# untitled.net
KiCad netlist of a schematic drawn in EAGLE
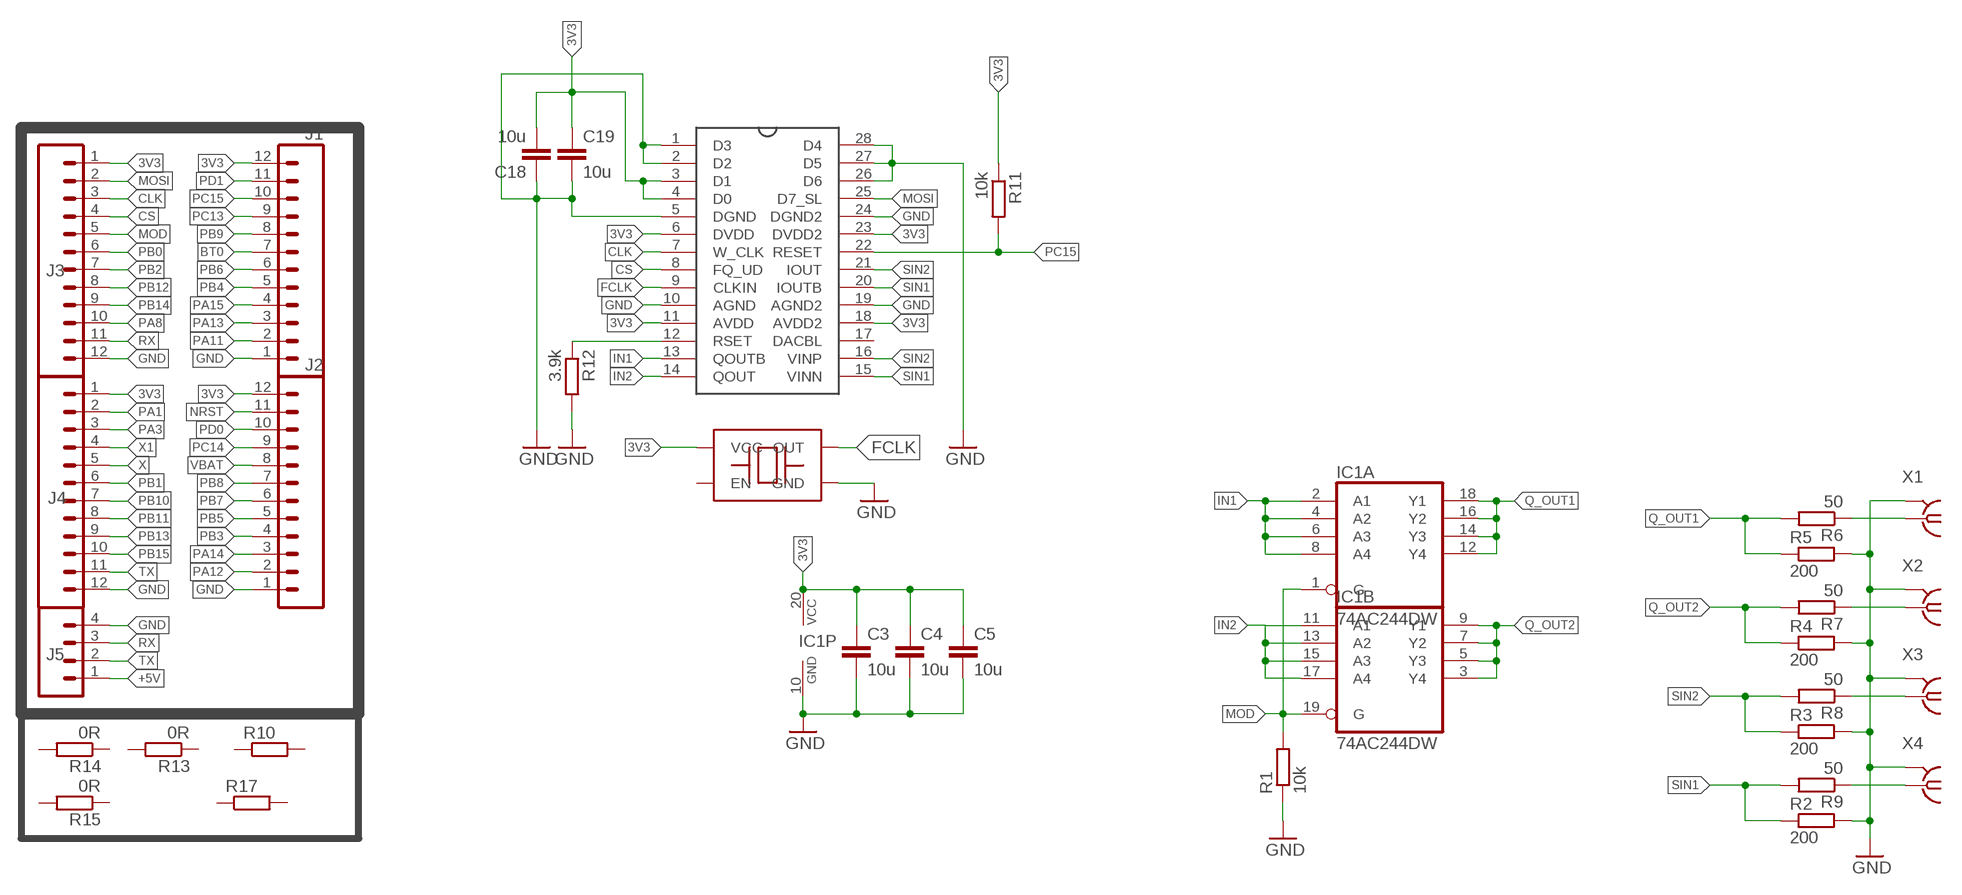
[diagram p0: schematic, sheet 1]

(export (version "E")
  (design (tool "Eeschema 10.0.6"))
  (components
    (comp (ref "C3")
      (value "10u")
      (footprint "eagle-import:0805")
      (libsource (lib "eagle-import") (part "C0805"))
    )
    (comp (ref "C4")
      (value "10u")
      (footprint "eagle-import:0805")
      (libsource (lib "eagle-import") (part "C0805"))
    )
    (comp (ref "C5")
      (value "10u")
      (footprint "eagle-import:0805")
      (libsource (lib "eagle-import") (part "C0805"))
    )
    (comp (ref "C18")
      (value "10u")
      (footprint "eagle-import:0805")
      (libsource (lib "eagle-import") (part "C0805"))
    )
    (comp (ref "C19")
      (value "10u")
      (footprint "eagle-import:0805")
      (libsource (lib "eagle-import") (part "C0805"))
    )
    (comp (ref "IC1")
      (value "74AC244DW")
      (footprint "eagle-import:SO20W")
      (libsource (lib "eagle-import") (part "74244DWAC"))
    )
    (comp (ref "J1")
      (value "M12PTH")
      (footprint "eagle-import:1X12")
      (libsource (lib "eagle-import") (part "M12PTH"))
    )
    (comp (ref "J2")
      (value "M12PTH")
      (footprint "eagle-import:1X12")
      (libsource (lib "eagle-import") (part "M12PTH"))
    )
    (comp (ref "J3")
      (value "M12PTH")
      (footprint "eagle-import:1X12")
      (libsource (lib "eagle-import") (part "M12PTH"))
    )
    (comp (ref "J4")
      (value "M12PTH")
      (footprint "eagle-import:1X12")
      (libsource (lib "eagle-import") (part "M12PTH"))
    )
    (comp (ref "J5")
      (value "M04PTH")
      (footprint "eagle-import:1X04")
      (libsource (lib "eagle-import") (part "M04PTH"))
    )
    (comp (ref "R1")
      (value "10k")
      (footprint "eagle-import:0805")
      (libsource (lib "eagle-import") (part "R0805"))
    )
    (comp (ref "R2")
      (value "200")
      (footprint "eagle-import:0805")
      (libsource (lib "eagle-import") (part "R0805"))
    )
    (comp (ref "R3")
      (value "200")
      (footprint "eagle-import:0805")
      (libsource (lib "eagle-import") (part "R0805"))
    )
    (comp (ref "R4")
      (value "200")
      (footprint "eagle-import:0805")
      (libsource (lib "eagle-import") (part "R0805"))
    )
    (comp (ref "R5")
      (value "200")
      (footprint "eagle-import:0805")
      (libsource (lib "eagle-import") (part "R0805"))
    )
    (comp (ref "R6")
      (value "50")
      (footprint "eagle-import:0805")
      (libsource (lib "eagle-import") (part "R0805"))
    )
    (comp (ref "R7")
      (value "50")
      (footprint "eagle-import:0805")
      (libsource (lib "eagle-import") (part "R0805"))
    )
    (comp (ref "R8")
      (value "50")
      (footprint "eagle-import:0805")
      (libsource (lib "eagle-import") (part "R0805"))
    )
    (comp (ref "R9")
      (value "50")
      (footprint "eagle-import:0805")
      (libsource (lib "eagle-import") (part "R0805"))
    )
    (comp (ref "R10")
      (value "R0805")
      (footprint "eagle-import:0805")
      (libsource (lib "eagle-import") (part "R0805"))
    )
    (comp (ref "R11")
      (value "10k")
      (footprint "eagle-import:0805")
      (libsource (lib "eagle-import") (part "R0805"))
    )
    (comp (ref "R12")
      (value "3.9k")
      (footprint "eagle-import:0805")
      (libsource (lib "eagle-import") (part "R0805"))
    )
    (comp (ref "R13")
      (value "0R")
      (footprint "eagle-import:0805")
      (libsource (lib "eagle-import") (part "R0805"))
    )
    (comp (ref "R14")
      (value "0R")
      (footprint "eagle-import:1206")
      (libsource (lib "eagle-import") (part "R1206"))
    )
    (comp (ref "R15")
      (value "0R")
      (footprint "eagle-import:0805")
      (libsource (lib "eagle-import") (part "R0805"))
    )
    (comp (ref "R17")
      (value "R1206")
      (footprint "eagle-import:1206")
      (libsource (lib "eagle-import") (part "R1206"))
    )
    (comp (ref "U$1")
      (value "AD9850")
      (footprint "eagle-import:SSOP28")
      (libsource (lib "eagle-import") (part "AD9850"))
    )
    (comp (ref "U$3")
      (value "TXC-BA")
      (footprint "eagle-import:7X5")
      (libsource (lib "eagle-import") (part "TXC-BA"))
    )
    (comp (ref "X1")
      (value "BU-SMA-H")
      (footprint "eagle-import:BU-SMA-H")
      (libsource (lib "eagle-import") (part "BU-SMA-H"))
    )
    (comp (ref "X2")
      (value "BU-SMA-H")
      (footprint "eagle-import:BU-SMA-H")
      (libsource (lib "eagle-import") (part "BU-SMA-H"))
    )
    (comp (ref "X3")
      (value "BU-SMA-H")
      (footprint "eagle-import:BU-SMA-H")
      (libsource (lib "eagle-import") (part "BU-SMA-H"))
    )
    (comp (ref "X4")
      (value "BU-SMA-H")
      (footprint "eagle-import:BU-SMA-H")
      (libsource (lib "eagle-import") (part "BU-SMA-H"))
    )
  )
  (nets
    (net (code "1") (name "+5V") (class "Default")
      (node (ref "J5") (pin "1") (pinfunction "1_1") (pintype "passive"))
    )
    (net (code "2") (name "3V3") (class "Default")
      (node (ref "C18") (pin "2") (pinfunction "2_2") (pintype "passive"))
      (node (ref "C19") (pin "1") (pinfunction "1_1") (pintype "passive"))
      (node (ref "C3") (pin "1") (pinfunction "1_1") (pintype "passive"))
      (node (ref "C4") (pin "1") (pinfunction "1_1") (pintype "passive"))
      (node (ref "C5") (pin "1") (pinfunction "1_1") (pintype "passive"))
      (node (ref "IC1") (pin "20") (pinfunction "VCC_20") (pintype "power_in"))
      (node (ref "J1") (pin "12") (pinfunction "12_12") (pintype "passive"))
      (node (ref "J2") (pin "12") (pinfunction "12_12") (pintype "passive"))
      (node (ref "J3") (pin "1") (pinfunction "1_1") (pintype "passive"))
      (node (ref "J4") (pin "1") (pinfunction "1_1") (pintype "passive"))
      (node (ref "R11") (pin "1") (pinfunction "1_1") (pintype "passive"))
      (node (ref "U$1") (pin "11") (pinfunction "AVDD_11") (pintype "power_in"))
      (node (ref "U$1") (pin "18") (pinfunction "AVDD2_18") (pintype "power_in"))
      (node (ref "U$1") (pin "23") (pinfunction "DVDD2_23") (pintype "power_in"))
      (node (ref "U$1") (pin "3") (pinfunction "D1_3") (pintype "input"))
      (node (ref "U$1") (pin "4") (pinfunction "D0_4") (pintype "bidirectional"))
      (node (ref "U$1") (pin "6") (pinfunction "DVDD_6") (pintype "power_in"))
      (node (ref "U$3") (pin "VCC") (pinfunction "VCC_VCC") (pintype "bidirectional"))
    )
    (net (code "3") (name "BT0") (class "Default")
      (node (ref "J1") (pin "7") (pinfunction "7_7") (pintype "passive"))
    )
    (net (code "4") (name "CLK") (class "Default")
      (node (ref "J3") (pin "3") (pinfunction "3_3") (pintype "passive"))
      (node (ref "U$1") (pin "7") (pinfunction "W_CLK_7") (pintype "bidirectional"))
    )
    (net (code "5") (name "CS") (class "Default")
      (node (ref "J3") (pin "4") (pinfunction "4_4") (pintype "passive"))
      (node (ref "U$1") (pin "8") (pinfunction "FQ_UD_8") (pintype "bidirectional"))
    )
    (net (code "6") (name "FCLK") (class "Default")
      (node (ref "U$1") (pin "9") (pinfunction "CLKIN_9") (pintype "input"))
      (node (ref "U$3") (pin "OUT") (pinfunction "OUT_OUT") (pintype "bidirectional"))
    )
    (net (code "7") (name "GND") (class "Default")
      (node (ref "C18") (pin "1") (pinfunction "1_1") (pintype "passive"))
      (node (ref "C19") (pin "2") (pinfunction "2_2") (pintype "passive"))
      (node (ref "C3") (pin "2") (pinfunction "2_2") (pintype "passive"))
      (node (ref "C4") (pin "2") (pinfunction "2_2") (pintype "passive"))
      (node (ref "C5") (pin "2") (pinfunction "2_2") (pintype "passive"))
      (node (ref "IC1") (pin "10") (pinfunction "GND_10") (pintype "power_in"))
      (node (ref "J1") (pin "1") (pinfunction "1_1") (pintype "passive"))
      (node (ref "J2") (pin "1") (pinfunction "1_1") (pintype "passive"))
      (node (ref "J3") (pin "12") (pinfunction "12_12") (pintype "passive"))
      (node (ref "J4") (pin "12") (pinfunction "12_12") (pintype "passive"))
      (node (ref "J5") (pin "4") (pinfunction "4_4") (pintype "passive"))
      (node (ref "R1") (pin "1") (pinfunction "1_1") (pintype "passive"))
      (node (ref "R12") (pin "2") (pinfunction "2_2") (pintype "passive"))
      (node (ref "R2") (pin "2") (pinfunction "2_2") (pintype "passive"))
      (node (ref "R3") (pin "2") (pinfunction "2_2") (pintype "passive"))
      (node (ref "R4") (pin "2") (pinfunction "2_2") (pintype "passive"))
      (node (ref "R5") (pin "2") (pinfunction "2_2") (pintype "passive"))
      (node (ref "U$1") (pin "1") (pinfunction "D3_1") (pintype "input"))
      (node (ref "U$1") (pin "10") (pinfunction "AGND_10") (pintype "power_in"))
      (node (ref "U$1") (pin "19") (pinfunction "AGND2_19") (pintype "power_in"))
      (node (ref "U$1") (pin "2") (pinfunction "D2_2") (pintype "input"))
      (node (ref "U$1") (pin "24") (pinfunction "DGND2_24") (pintype "power_in"))
      (node (ref "U$1") (pin "26") (pinfunction "D6_26") (pintype "input"))
      (node (ref "U$1") (pin "27") (pinfunction "D5_27") (pintype "input"))
      (node (ref "U$1") (pin "28") (pinfunction "D4_28") (pintype "input"))
      (node (ref "U$1") (pin "5") (pinfunction "DGND_5") (pintype "power_in"))
      (node (ref "U$3") (pin "GND") (pinfunction "GND_GND") (pintype "bidirectional"))
      (node (ref "X1") (pin "2") (pinfunction "2_2") (pintype "passive"))
      (node (ref "X1") (pin "3") (pinfunction "2_3") (pintype "passive"))
      (node (ref "X1") (pin "4") (pinfunction "2_4") (pintype "passive"))
      (node (ref "X1") (pin "5") (pinfunction "2_5") (pintype "passive"))
      (node (ref "X2") (pin "2") (pinfunction "2_2") (pintype "passive"))
      (node (ref "X2") (pin "3") (pinfunction "2_3") (pintype "passive"))
      (node (ref "X2") (pin "4") (pinfunction "2_4") (pintype "passive"))
      (node (ref "X2") (pin "5") (pinfunction "2_5") (pintype "passive"))
      (node (ref "X3") (pin "2") (pinfunction "2_2") (pintype "passive"))
      (node (ref "X3") (pin "3") (pinfunction "2_3") (pintype "passive"))
      (node (ref "X3") (pin "4") (pinfunction "2_4") (pintype "passive"))
      (node (ref "X3") (pin "5") (pinfunction "2_5") (pintype "passive"))
      (node (ref "X4") (pin "2") (pinfunction "2_2") (pintype "passive"))
      (node (ref "X4") (pin "3") (pinfunction "2_3") (pintype "passive"))
      (node (ref "X4") (pin "4") (pinfunction "2_4") (pintype "passive"))
      (node (ref "X4") (pin "5") (pinfunction "2_5") (pintype "passive"))
    )
    (net (code "8") (name "IN1") (class "Default")
      (node (ref "IC1") (pin "2") (pinfunction "A1_2") (pintype "input"))
      (node (ref "IC1") (pin "4") (pinfunction "A2_4") (pintype "input"))
      (node (ref "IC1") (pin "6") (pinfunction "A3_6") (pintype "input"))
      (node (ref "IC1") (pin "8") (pinfunction "A4_8") (pintype "input"))
      (node (ref "U$1") (pin "13") (pinfunction "QOUTB_13") (pintype "output"))
    )
    (net (code "9") (name "IN2") (class "Default")
      (node (ref "IC1") (pin "11") (pinfunction "A1_11") (pintype "input"))
      (node (ref "IC1") (pin "13") (pinfunction "A2_13") (pintype "input"))
      (node (ref "IC1") (pin "15") (pinfunction "A3_15") (pintype "input"))
      (node (ref "IC1") (pin "17") (pinfunction "A4_17") (pintype "input"))
      (node (ref "U$1") (pin "14") (pinfunction "QOUT_14") (pintype "output"))
    )
    (net (code "10") (name "MOD") (class "Default")
      (node (ref "IC1") (pin "1") (pinfunction "G_1") (pintype "input"))
      (node (ref "IC1") (pin "19") (pinfunction "G_19") (pintype "input"))
      (node (ref "J3") (pin "5") (pinfunction "5_5") (pintype "passive"))
      (node (ref "R1") (pin "2") (pinfunction "2_2") (pintype "passive"))
    )
    (net (code "11") (name "MOSI") (class "Default")
      (node (ref "J3") (pin "2") (pinfunction "2_2") (pintype "passive"))
      (node (ref "U$1") (pin "25") (pinfunction "D7_SL_25") (pintype "input"))
    )
    (net (code "12") (name "NRST") (class "Default")
      (node (ref "J2") (pin "11") (pinfunction "11_11") (pintype "passive"))
    )
    (net (code "13") (name "Net-(R6-Pad1)") (class "Default")
      (node (ref "R6") (pin "1") (pinfunction "1_1") (pintype "passive"))
      (node (ref "X1") (pin "1") (pinfunction "1_1") (pintype "passive"))
    )
    (net (code "14") (name "Net-(R7-Pad1)") (class "Default")
      (node (ref "R7") (pin "1") (pinfunction "1_1") (pintype "passive"))
      (node (ref "X2") (pin "1") (pinfunction "1_1") (pintype "passive"))
    )
    (net (code "15") (name "Net-(R8-Pad1)") (class "Default")
      (node (ref "R8") (pin "1") (pinfunction "1_1") (pintype "passive"))
      (node (ref "X3") (pin "1") (pinfunction "1_1") (pintype "passive"))
    )
    (net (code "16") (name "Net-(R9-Pad1)") (class "Default")
      (node (ref "R9") (pin "1") (pinfunction "1_1") (pintype "passive"))
      (node (ref "X4") (pin "1") (pinfunction "1_1") (pintype "passive"))
    )
    (net (code "17") (name "Net-(U$1-RSET)") (class "Default")
      (node (ref "R12") (pin "1") (pinfunction "1_1") (pintype "passive"))
      (node (ref "U$1") (pin "12") (pinfunction "RSET_12") (pintype "input"))
    )
    (net (code "18") (name "PA1") (class "Default")
      (node (ref "J4") (pin "2") (pinfunction "2_2") (pintype "passive"))
    )
    (net (code "19") (name "PA3") (class "Default")
      (node (ref "J4") (pin "3") (pinfunction "3_3") (pintype "passive"))
    )
    (net (code "20") (name "PA8") (class "Default")
      (node (ref "J3") (pin "10") (pinfunction "10_10") (pintype "passive"))
    )
    (net (code "21") (name "PA11") (class "Default")
      (node (ref "J1") (pin "2") (pinfunction "2_2") (pintype "passive"))
    )
    (net (code "22") (name "PA12") (class "Default")
      (node (ref "J2") (pin "2") (pinfunction "2_2") (pintype "passive"))
    )
    (net (code "23") (name "PA13") (class "Default")
      (node (ref "J1") (pin "3") (pinfunction "3_3") (pintype "passive"))
    )
    (net (code "24") (name "PA14") (class "Default")
      (node (ref "J2") (pin "3") (pinfunction "3_3") (pintype "passive"))
    )
    (net (code "25") (name "PA15") (class "Default")
      (node (ref "J1") (pin "4") (pinfunction "4_4") (pintype "passive"))
    )
    (net (code "26") (name "PB0") (class "Default")
      (node (ref "J3") (pin "6") (pinfunction "6_6") (pintype "passive"))
    )
    (net (code "27") (name "PB1") (class "Default")
      (node (ref "J4") (pin "6") (pinfunction "6_6") (pintype "passive"))
    )
    (net (code "28") (name "PB2") (class "Default")
      (node (ref "J3") (pin "7") (pinfunction "7_7") (pintype "passive"))
    )
    (net (code "29") (name "PB3") (class "Default")
      (node (ref "J2") (pin "4") (pinfunction "4_4") (pintype "passive"))
    )
    (net (code "30") (name "PB4") (class "Default")
      (node (ref "J1") (pin "5") (pinfunction "5_5") (pintype "passive"))
    )
    (net (code "31") (name "PB5") (class "Default")
      (node (ref "J2") (pin "5") (pinfunction "5_5") (pintype "passive"))
    )
    (net (code "32") (name "PB6") (class "Default")
      (node (ref "J1") (pin "6") (pinfunction "6_6") (pintype "passive"))
    )
    (net (code "33") (name "PB7") (class "Default")
      (node (ref "J2") (pin "6") (pinfunction "6_6") (pintype "passive"))
    )
    (net (code "34") (name "PB8") (class "Default")
      (node (ref "J2") (pin "7") (pinfunction "7_7") (pintype "passive"))
    )
    (net (code "35") (name "PB9") (class "Default")
      (node (ref "J1") (pin "8") (pinfunction "8_8") (pintype "passive"))
    )
    (net (code "36") (name "PB10") (class "Default")
      (node (ref "J4") (pin "7") (pinfunction "7_7") (pintype "passive"))
    )
    (net (code "37") (name "PB11") (class "Default")
      (node (ref "J4") (pin "8") (pinfunction "8_8") (pintype "passive"))
    )
    (net (code "38") (name "PB12") (class "Default")
      (node (ref "J3") (pin "8") (pinfunction "8_8") (pintype "passive"))
    )
    (net (code "39") (name "PB13") (class "Default")
      (node (ref "J4") (pin "9") (pinfunction "9_9") (pintype "passive"))
    )
    (net (code "40") (name "PB14") (class "Default")
      (node (ref "J3") (pin "9") (pinfunction "9_9") (pintype "passive"))
    )
    (net (code "41") (name "PB15") (class "Default")
      (node (ref "J4") (pin "10") (pinfunction "10_10") (pintype "passive"))
    )
    (net (code "42") (name "PC13") (class "Default")
      (node (ref "J1") (pin "9") (pinfunction "9_9") (pintype "passive"))
    )
    (net (code "43") (name "PC14") (class "Default")
      (node (ref "J2") (pin "9") (pinfunction "9_9") (pintype "passive"))
    )
    (net (code "44") (name "PC15") (class "Default")
      (node (ref "J1") (pin "10") (pinfunction "10_10") (pintype "passive"))
      (node (ref "R11") (pin "2") (pinfunction "2_2") (pintype "passive"))
      (node (ref "U$1") (pin "22") (pinfunction "RESET_22") (pintype "input"))
    )
    (net (code "45") (name "PD0") (class "Default")
      (node (ref "J2") (pin "10") (pinfunction "10_10") (pintype "passive"))
    )
    (net (code "46") (name "PD1") (class "Default")
      (node (ref "J1") (pin "11") (pinfunction "11_11") (pintype "passive"))
    )
    (net (code "47") (name "Q_OUT1") (class "Default")
      (node (ref "IC1") (pin "12") (pinfunction "Y4_12") (pintype "tri_state"))
      (node (ref "IC1") (pin "14") (pinfunction "Y3_14") (pintype "tri_state"))
      (node (ref "IC1") (pin "16") (pinfunction "Y2_16") (pintype "tri_state"))
      (node (ref "IC1") (pin "18") (pinfunction "Y1_18") (pintype "tri_state"))
      (node (ref "R5") (pin "1") (pinfunction "1_1") (pintype "passive"))
      (node (ref "R6") (pin "2") (pinfunction "2_2") (pintype "passive"))
    )
    (net (code "48") (name "Q_OUT2") (class "Default")
      (node (ref "IC1") (pin "3") (pinfunction "Y4_3") (pintype "tri_state"))
      (node (ref "IC1") (pin "5") (pinfunction "Y3_5") (pintype "tri_state"))
      (node (ref "IC1") (pin "7") (pinfunction "Y2_7") (pintype "tri_state"))
      (node (ref "IC1") (pin "9") (pinfunction "Y1_9") (pintype "tri_state"))
      (node (ref "R4") (pin "1") (pinfunction "1_1") (pintype "passive"))
      (node (ref "R7") (pin "2") (pinfunction "2_2") (pintype "passive"))
    )
    (net (code "49") (name "RX") (class "Default")
      (node (ref "J3") (pin "11") (pinfunction "11_11") (pintype "passive"))
      (node (ref "J5") (pin "3") (pinfunction "3_3") (pintype "passive"))
    )
    (net (code "50") (name "SIN1") (class "Default")
      (node (ref "R2") (pin "1") (pinfunction "1_1") (pintype "passive"))
      (node (ref "R9") (pin "2") (pinfunction "2_2") (pintype "passive"))
      (node (ref "U$1") (pin "15") (pinfunction "VINN_15") (pintype "input"))
      (node (ref "U$1") (pin "20") (pinfunction "IOUTB_20") (pintype "output"))
    )
    (net (code "51") (name "SIN2") (class "Default")
      (node (ref "R3") (pin "1") (pinfunction "1_1") (pintype "passive"))
      (node (ref "R8") (pin "2") (pinfunction "2_2") (pintype "passive"))
      (node (ref "U$1") (pin "16") (pinfunction "VINP_16") (pintype "input"))
      (node (ref "U$1") (pin "21") (pinfunction "IOUT_21") (pintype "output"))
    )
    (net (code "52") (name "TX") (class "Default")
      (node (ref "J4") (pin "11") (pinfunction "11_11") (pintype "passive"))
      (node (ref "J5") (pin "2") (pinfunction "2_2") (pintype "passive"))
    )
    (net (code "53") (name "VBAT") (class "Default")
      (node (ref "J2") (pin "8") (pinfunction "8_8") (pintype "passive"))
    )
    (net (code "54") (name "X") (class "Default")
      (node (ref "J4") (pin "5") (pinfunction "5_5") (pintype "passive"))
    )
    (net (code "55") (name "X1") (class "Default")
      (node (ref "J4") (pin "4") (pinfunction "4_4") (pintype "passive"))
    )
    (net (code "56") (name "unconnected-(R10-Pad1)") (class "Default")
      (node (ref "R10") (pin "1") (pinfunction "1_1") (pintype "passive"))
    )
    (net (code "57") (name "unconnected-(R10-Pad2)") (class "Default")
      (node (ref "R10") (pin "2") (pinfunction "2_2") (pintype "passive"))
    )
    (net (code "58") (name "unconnected-(R13-Pad1)") (class "Default")
      (node (ref "R13") (pin "1") (pinfunction "1_1") (pintype "passive"))
    )
    (net (code "59") (name "unconnected-(R13-Pad2)") (class "Default")
      (node (ref "R13") (pin "2") (pinfunction "2_2") (pintype "passive"))
    )
    (net (code "60") (name "unconnected-(R14-Pad1)") (class "Default")
      (node (ref "R14") (pin "1") (pinfunction "1_1") (pintype "passive"))
    )
    (net (code "61") (name "unconnected-(R14-Pad2)") (class "Default")
      (node (ref "R14") (pin "2") (pinfunction "2_2") (pintype "passive"))
    )
    (net (code "62") (name "unconnected-(R15-Pad1)") (class "Default")
      (node (ref "R15") (pin "1") (pinfunction "1_1") (pintype "passive"))
    )
    (net (code "63") (name "unconnected-(R15-Pad2)") (class "Default")
      (node (ref "R15") (pin "2") (pinfunction "2_2") (pintype "passive"))
    )
    (net (code "64") (name "unconnected-(R17-Pad1)") (class "Default")
      (node (ref "R17") (pin "1") (pinfunction "1_1") (pintype "passive"))
    )
    (net (code "65") (name "unconnected-(R17-Pad2)") (class "Default")
      (node (ref "R17") (pin "2") (pinfunction "2_2") (pintype "passive"))
    )
    (net (code "66") (name "unconnected-(U$1-DACBL-Pad17)") (class "Default")
      (node (ref "U$1") (pin "17") (pinfunction "DACBL_17") (pintype "no_connect"))
    )
    (net (code "67") (name "unconnected-(U$3-PadEN)") (class "Default")
      (node (ref "U$3") (pin "EN") (pinfunction "EN_EN") (pintype "bidirectional"))
    )
  )
)
